# valves.net
KiCad netlist of a schematic drawn in Altium Designer
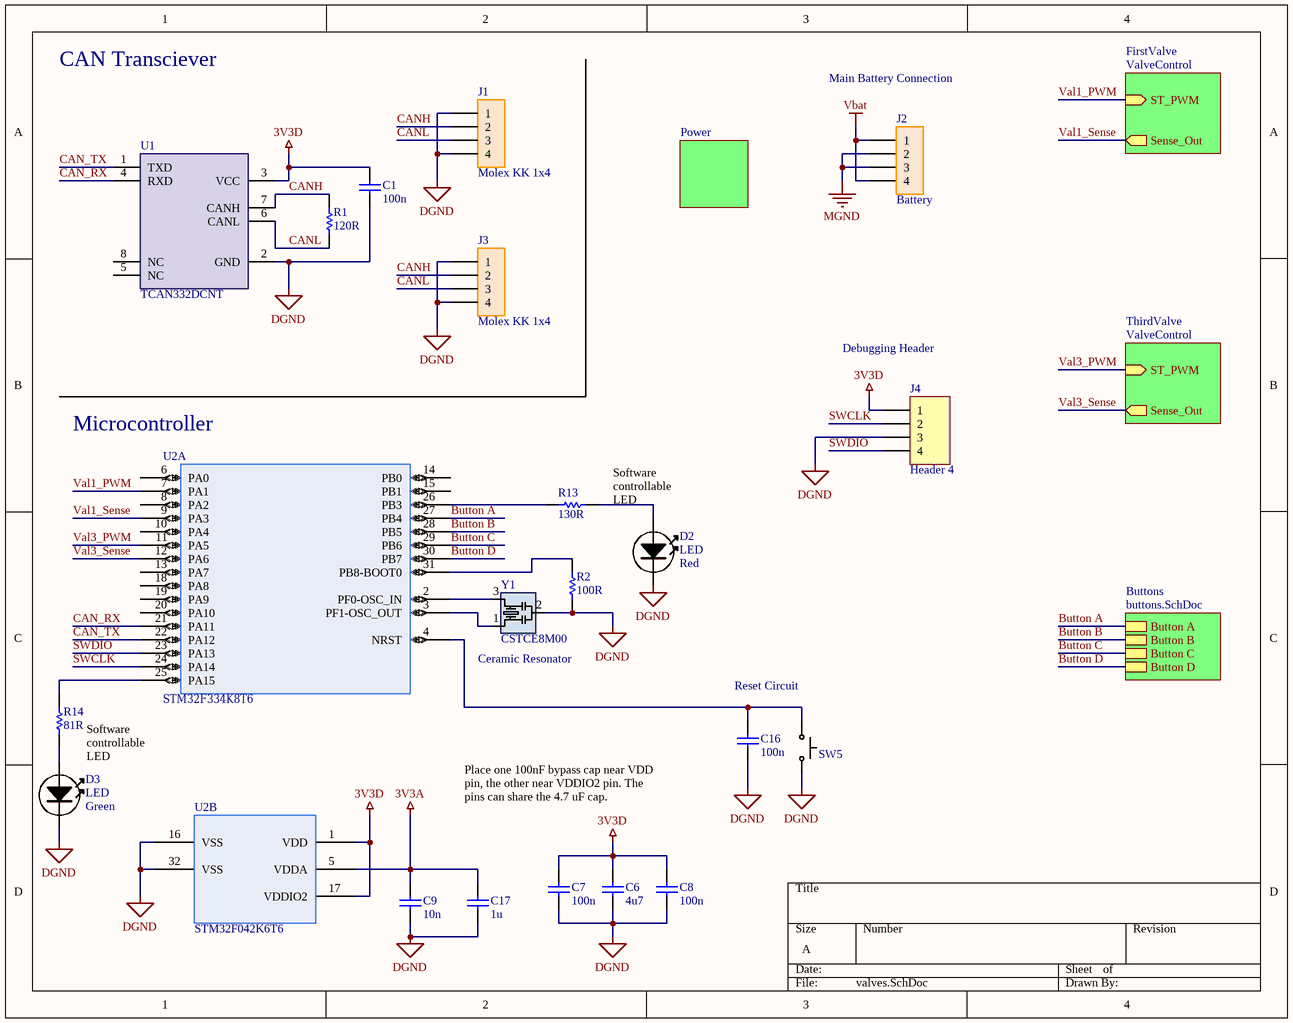
[diagram p0: valves.SchDoc]

(export (version "E")
  (design (tool "Eeschema 10.0.6"))
  (components
    (comp (ref "C1")
      (value "100n")
      (footprint "C0805_med_density")
      (description "SMD Ceramic Capacitor")
      (fields (field (name "Comment") "CapCer"))
      (libsource (lib "passives") (part "CapCer"))
    )
    (comp (ref "C6")
      (value "4u7")
      (footprint "C0603_med_density")
      (description "SMD Ceramic Capacitor")
      (fields (field (name "Comment") "CapCer"))
      (libsource (lib "passives") (part "CapCer"))
    )
    (comp (ref "C7")
      (value "100n")
      (footprint "C0603_med_density")
      (description "SMD Ceramic Capacitor")
      (fields (field (name "Comment") "CapCer"))
      (libsource (lib "passives") (part "CapCer"))
    )
    (comp (ref "C8")
      (value "100n")
      (footprint "C0603_med_density")
      (description "SMD Ceramic Capacitor")
      (fields (field (name "Comment") "CapCer"))
      (libsource (lib "passives") (part "CapCer"))
    )
    (comp (ref "C9")
      (value "10n")
      (footprint "C0603_med_density")
      (description "SMD Ceramic Capacitor")
      (fields (field (name "Comment") "CapCer"))
      (libsource (lib "passives") (part "CapCer"))
    )
    (comp (ref "C16")
      (value "100n")
      (footprint "C0805_med_density")
      (description "SMD Ceramic Capacitor")
      (fields (field (name "Comment") "CapCer"))
      (libsource (lib "passives") (part "CapCer"))
    )
    (comp (ref "C17")
      (value "1u")
      (footprint "C0603_med_density")
      (description "SMD Ceramic Capacitor")
      (fields (field (name "Comment") "CapCer"))
      (libsource (lib "passives") (part "CapCer"))
    )
    (comp (ref "D2")
      (value "LED")
      (footprint "LED0805")
      (description "Light-emitting diode")
      (fields (field (name "ALTIUM_VALUE") "Red"))
      (libsource (lib "passives") (part "LED"))
    )
    (comp (ref "D3")
      (value "LED")
      (footprint "LED0805")
      (description "Light-emitting diode")
      (fields (field (name "ALTIUM_VALUE") "Green"))
      (libsource (lib "passives") (part "LED"))
    )
    (comp (ref "J1")
      (value "Molex KK 1x4")
      (footprint "Molex KK 4x1")
      (description "1x4 Molex KK Connector (CAN)")
      (libsource (lib "connectors") (part "Molex KK 1x4"))
    )
    (comp (ref "J2")
      (value "Battery")
      (footprint "CON_2074781004_MOL")
      (description "Molex 1x4 11A Connector")
      (fields
        (field (name "MANUFACTURER_PART_NUMBER") "2074781004")
        (field (name "COPYRIGHT") "Copyright (C) 2018 Accelerated Designs. All rights reserved")
      )
      (libsource (lib "connectors") (part "2074781004"))
    )
    (comp (ref "J3")
      (value "Molex KK 1x4")
      (footprint "Molex KK 4x1")
      (description "1x4 Molex KK Connector (CAN)")
      (libsource (lib "connectors") (part "Molex KK 1x4"))
    )
    (comp (ref "J4")
      (value "Header 4")
      (footprint "HDR1X4")
      (description "Header, 4-Pin")
      (fields (field (name "PUBLISHER") "Altium Limited"))
      (libsource (lib "Miscellaneous Connectors") (part "Header 4"))
    )
    (comp (ref "R1")
      (value "120R")
      (footprint "R0805_med_density")
      (description "SMD Chip resistor")
      (fields (field (name "Comment") "ResChip"))
      (libsource (lib "passives") (part "ResChip"))
    )
    (comp (ref "R2")
      (value "100R")
      (footprint "R0805_med_density")
      (description "SMD Chip resistor")
      (fields (field (name "TOLERANCE") "1%") (field (name "Comment") "ResChip"))
      (libsource (lib "passives") (part "ResChip"))
    )
    (comp (ref "R13")
      (value "130R")
      (footprint "R0603_med_density")
      (description "SMD Chip resistor")
      (fields (field (name "Comment") "ResChip"))
      (libsource (lib "passives") (part "ResChip"))
    )
    (comp (ref "R14")
      (value "81R")
      (footprint "R0603_med_density")
      (description "SMD Chip resistor")
      (fields (field (name "Comment") "ResChip"))
      (libsource (lib "passives") (part "ResChip"))
    )
    (comp (ref "SW5")
      (value "Switch")
      (footprint "PUSHBUTTON")
      (description "Push button switch, momentary, normally open")
      (libsource (lib "valves") (part "Switch"))
    )
    (comp (ref "U1")
      (value "TCAN332DCNT")
      (footprint "SOT-23-8")
      (description "IC TXRX CAN 3.3V SOT23-8")
      (libsource (lib "valves") (part "TCAN332DCNT"))
    )
    (comp (ref "U2")
      (value "STM32F334K8T6‎")
      (footprint "LQFP-32")
      (description "STM32 MCU")
      (fields (field (name "COPYRIGHT") "Copyright (C) 2018 Accelerated Designs. All rights reserved"))
      (libsource (lib "") (part "STM32F042K6T6_1"))
    )
    (comp (ref "Y1")
      (value "CSTCE8M00")
      (footprint "8MHz Ceramic Resonator")
      (description "8MHz Ceramic Resonator")
      (libsource (lib "valves") (part "CSTCE8M00"))
    )
  )
  (nets
    (net (code "1") (name "/Button A") (class "Default")
      (node (ref "U2") (pin "27") (pinfunction "PB4_27") (pintype "bidirectional"))
    )
    (net (code "2") (name "/Button B") (class "Default")
      (node (ref "U2") (pin "28") (pinfunction "PB5_28") (pintype "bidirectional"))
    )
    (net (code "3") (name "/Button C") (class "Default")
      (node (ref "U2") (pin "29") (pinfunction "PB6_29") (pintype "bidirectional"))
    )
    (net (code "4") (name "/Button D") (class "Default")
      (node (ref "U2") (pin "30") (pinfunction "PB7_30") (pintype "bidirectional"))
    )
    (net (code "5") (name "/CANH") (class "Default")
      (node (ref "J1") (pin "2") (pinfunction "2_2") (pintype "passive"))
      (node (ref "J3") (pin "2") (pinfunction "2_2") (pintype "passive"))
      (node (ref "R1") (pin "1") (pinfunction "1_1") (pintype "passive"))
      (node (ref "U1") (pin "7") (pinfunction "CANH_7") (pintype "passive"))
    )
    (net (code "6") (name "/CANL") (class "Default")
      (node (ref "J1") (pin "3") (pinfunction "3_3") (pintype "passive"))
      (node (ref "J3") (pin "3") (pinfunction "3_3") (pintype "passive"))
      (node (ref "R1") (pin "2") (pinfunction "2_2") (pintype "passive"))
      (node (ref "U1") (pin "6") (pinfunction "CANL_6") (pintype "passive"))
    )
    (net (code "7") (name "/CAN_RX") (class "Default")
      (node (ref "U1") (pin "4") (pinfunction "RXD_4") (pintype "passive"))
      (node (ref "U2") (pin "21") (pinfunction "PA11_21") (pintype "bidirectional"))
    )
    (net (code "8") (name "/CAN_TX") (class "Default")
      (node (ref "U1") (pin "1") (pinfunction "TXD_1") (pintype "passive"))
      (node (ref "U2") (pin "22") (pinfunction "PA12_22") (pintype "bidirectional"))
    )
    (net (code "9") (name "/SWCLK") (class "Default")
      (node (ref "J4") (pin "2") (pinfunction "2_2") (pintype "passive"))
      (node (ref "U2") (pin "24") (pinfunction "PA14_24") (pintype "bidirectional"))
    )
    (net (code "10") (name "/SWDIO") (class "Default")
      (node (ref "J4") (pin "4") (pinfunction "4_4") (pintype "passive"))
      (node (ref "U2") (pin "23") (pinfunction "PA13_23") (pintype "bidirectional"))
    )
    (net (code "11") (name "/Val1_PWM") (class "Default")
      (node (ref "U2") (pin "7") (pinfunction "PA1_7") (pintype "bidirectional"))
    )
    (net (code "12") (name "/Val1_Sense") (class "Default")
      (node (ref "U2") (pin "9") (pinfunction "PA3_9") (pintype "bidirectional"))
    )
    (net (code "13") (name "/Val3_PWM") (class "Default")
      (node (ref "U2") (pin "11") (pinfunction "PA5_11") (pintype "bidirectional"))
    )
    (net (code "14") (name "/Val3_Sense") (class "Default")
      (node (ref "U2") (pin "12") (pinfunction "PA6_12") (pintype "bidirectional"))
    )
    (net (code "15") (name "3V3A") (class "Default")
      (node (ref "C17") (pin "1") (pinfunction "1_1") (pintype "passive"))
      (node (ref "C9") (pin "1") (pinfunction "1_1") (pintype "passive"))
      (node (ref "U2") (pin "5") (pinfunction "VDDA_5") (pintype "power_in"))
    )
    (net (code "16") (name "3V3D") (class "Default")
      (node (ref "C1") (pin "1") (pinfunction "1_1") (pintype "passive"))
      (node (ref "C6") (pin "2") (pinfunction "2_2") (pintype "passive"))
      (node (ref "C7") (pin "2") (pinfunction "2_2") (pintype "passive"))
      (node (ref "C8") (pin "2") (pinfunction "2_2") (pintype "passive"))
      (node (ref "J4") (pin "1") (pinfunction "1_1") (pintype "passive"))
      (node (ref "U1") (pin "3") (pinfunction "VCC_3") (pintype "passive"))
      (node (ref "U2") (pin "1") (pinfunction "VDD_1") (pintype "power_in"))
      (node (ref "U2") (pin "17") (pinfunction "VDDIO2_17") (pintype "power_in"))
    )
    (net (code "17") (name "DGND") (class "Default")
      (node (ref "C1") (pin "2") (pinfunction "2_2") (pintype "passive"))
      (node (ref "C16") (pin "1") (pinfunction "1_1") (pintype "passive"))
      (node (ref "C17") (pin "2") (pinfunction "2_2") (pintype "passive"))
      (node (ref "C6") (pin "1") (pinfunction "1_1") (pintype "passive"))
      (node (ref "C7") (pin "1") (pinfunction "1_1") (pintype "passive"))
      (node (ref "C8") (pin "1") (pinfunction "1_1") (pintype "passive"))
      (node (ref "C9") (pin "2") (pinfunction "2_2") (pintype "passive"))
      (node (ref "D2") (pin "K") (pintype "passive"))
      (node (ref "D3") (pin "K") (pintype "passive"))
      (node (ref "J1") (pin "1") (pinfunction "1_1") (pintype "passive"))
      (node (ref "J1") (pin "4") (pinfunction "4_4") (pintype "passive"))
      (node (ref "J3") (pin "1") (pinfunction "1_1") (pintype "passive"))
      (node (ref "J3") (pin "4") (pinfunction "4_4") (pintype "passive"))
      (node (ref "J4") (pin "3") (pinfunction "3_3") (pintype "passive"))
      (node (ref "R2") (pin "1") (pinfunction "1_1") (pintype "passive"))
      (node (ref "SW5") (pin "1") (pinfunction "1_1") (pintype "passive"))
      (node (ref "U1") (pin "2") (pinfunction "GND_2") (pintype "passive"))
      (node (ref "U2") (pin "16") (pinfunction "VSS_16") (pintype "power_in"))
      (node (ref "U2") (pin "32") (pinfunction "VSS_32") (pintype "power_in"))
      (node (ref "Y1") (pin "2") (pinfunction "GND_2") (pintype "passive"))
    )
    (net (code "18") (name "MGND") (class "Default")
      (node (ref "J2") (pin "2") (pinfunction "2_2") (pintype "passive"))
      (node (ref "J2") (pin "3") (pinfunction "3_3") (pintype "passive"))
    )
    (net (code "19") (name "Net-(D2-PadA)") (class "Default")
      (node (ref "D2") (pin "A") (pintype "passive"))
      (node (ref "R13") (pin "1") (pinfunction "1_1") (pintype "passive"))
    )
    (net (code "20") (name "Net-(D3-PadA)") (class "Default")
      (node (ref "D3") (pin "A") (pintype "passive"))
      (node (ref "R14") (pin "1") (pinfunction "1_1") (pintype "passive"))
    )
    (net (code "21") (name "Net-(U2A-NRST)") (class "Default")
      (node (ref "C16") (pin "2") (pinfunction "2_2") (pintype "passive"))
      (node (ref "SW5") (pin "2") (pinfunction "2_2") (pintype "passive"))
      (node (ref "U2") (pin "4") (pinfunction "NRST_4") (pintype "bidirectional"))
    )
    (net (code "22") (name "Net-(U2A-PA15)") (class "Default")
      (node (ref "R14") (pin "2") (pinfunction "2_2") (pintype "passive"))
      (node (ref "U2") (pin "25") (pinfunction "PA15_25") (pintype "bidirectional"))
    )
    (net (code "23") (name "Net-(U2A-PB3)") (class "Default")
      (node (ref "R13") (pin "2") (pinfunction "2_2") (pintype "passive"))
      (node (ref "U2") (pin "26") (pinfunction "PB3_26") (pintype "bidirectional"))
    )
    (net (code "24") (name "Net-(U2A-PB8-BOOT0)") (class "Default")
      (node (ref "R2") (pin "2") (pinfunction "2_2") (pintype "passive"))
      (node (ref "U2") (pin "31") (pinfunction "PB8-BOOT0_31") (pintype "bidirectional"))
    )
    (net (code "25") (name "Net-(U2A-PF0-OSC_IN)") (class "Default")
      (node (ref "U2") (pin "2") (pinfunction "PF0-OSC_IN_2") (pintype "bidirectional"))
      (node (ref "Y1") (pin "3") (pinfunction "OSC2_3") (pintype "passive"))
    )
    (net (code "26") (name "Net-(U2A-PF1-OSC_OUT)") (class "Default")
      (node (ref "U2") (pin "3") (pinfunction "PF1-OSC_OUT_3") (pintype "bidirectional"))
      (node (ref "Y1") (pin "1") (pinfunction "OSC1_1") (pintype "passive"))
    )
    (net (code "27") (name "Vbat") (class "Default")
      (node (ref "J2") (pin "1") (pinfunction "1_1") (pintype "passive"))
      (node (ref "J2") (pin "4") (pinfunction "4_4") (pintype "passive"))
    )
    (net (code "28") (name "unconnected-(U1-NC-Pad5)") (class "Default")
      (node (ref "U1") (pin "5") (pinfunction "NC_5") (pintype "passive"))
    )
    (net (code "29") (name "unconnected-(U1-NC-Pad8)") (class "Default")
      (node (ref "U1") (pin "8") (pinfunction "NC_8") (pintype "passive"))
    )
    (net (code "30") (name "unconnected-(U2A-PA0-Pad6)") (class "Default")
      (node (ref "U2") (pin "6") (pinfunction "PA0_6") (pintype "bidirectional"))
    )
    (net (code "31") (name "unconnected-(U2A-PA2-Pad8)") (class "Default")
      (node (ref "U2") (pin "8") (pinfunction "PA2_8") (pintype "bidirectional"))
    )
    (net (code "32") (name "unconnected-(U2A-PA4-Pad10)") (class "Default")
      (node (ref "U2") (pin "10") (pinfunction "PA4_10") (pintype "bidirectional"))
    )
    (net (code "33") (name "unconnected-(U2A-PA7-Pad13)") (class "Default")
      (node (ref "U2") (pin "13") (pinfunction "PA7_13") (pintype "bidirectional"))
    )
    (net (code "34") (name "unconnected-(U2A-PA8-Pad18)") (class "Default")
      (node (ref "U2") (pin "18") (pinfunction "PA8_18") (pintype "bidirectional"))
    )
    (net (code "35") (name "unconnected-(U2A-PA9-Pad19)") (class "Default")
      (node (ref "U2") (pin "19") (pinfunction "PA9_19") (pintype "bidirectional"))
    )
    (net (code "36") (name "unconnected-(U2A-PA10-Pad20)") (class "Default")
      (node (ref "U2") (pin "20") (pinfunction "PA10_20") (pintype "bidirectional"))
    )
    (net (code "37") (name "unconnected-(U2A-PB0-Pad14)") (class "Default")
      (node (ref "U2") (pin "14") (pinfunction "PB0_14") (pintype "bidirectional"))
    )
    (net (code "38") (name "unconnected-(U2A-PB1-Pad15)") (class "Default")
      (node (ref "U2") (pin "15") (pinfunction "PB1_15") (pintype "bidirectional"))
    )
  )
)
